# Sheet1.net
KiCad netlist of a schematic drawn in Altium Designer
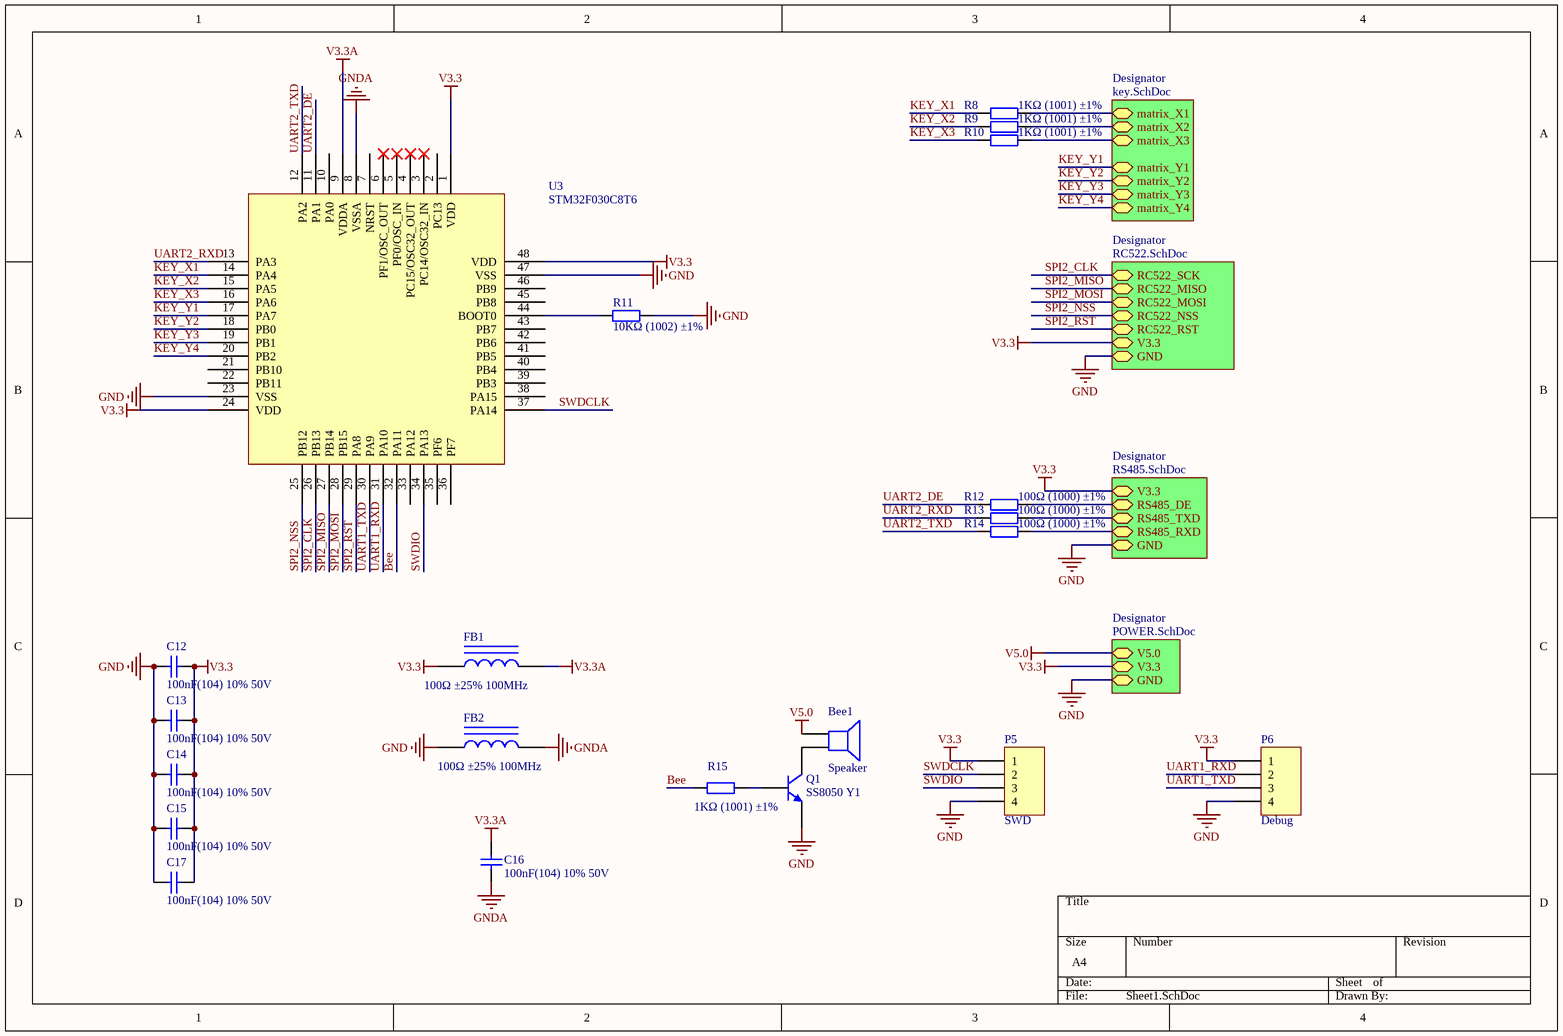
[diagram p0: Sheet1.SchDoc]

(export (version "E")
  (design (tool "Eeschema 10.0.6"))
  (components
    (comp (ref "Bee1")
      (value "Speaker")
      (footprint "Bee")
      (description "Loudspeaker")
      (fields (field (name "PUBLISHER") "Altium Limited"))
      (libsource (lib "Miscellaneous Devices") (part "Speaker"))
    )
    (comp (ref "C12")
      (value "100nF(104) 10% 50V")
      (footprint "0805_C")
      (description "贴片电容")
      (libsource (lib "Miscellaneous Devices LC") (part "0805 100nF(104) 10% 50V"))
    )
    (comp (ref "C13")
      (value "100nF(104) 10% 50V")
      (footprint "0805_C")
      (description "贴片电容")
      (libsource (lib "Miscellaneous Devices LC") (part "0805 100nF(104) 10% 50V"))
    )
    (comp (ref "C14")
      (value "100nF(104) 10% 50V")
      (footprint "0805_C")
      (description "贴片电容")
      (libsource (lib "Miscellaneous Devices LC") (part "0805 100nF(104) 10% 50V"))
    )
    (comp (ref "C15")
      (value "100nF(104) 10% 50V")
      (footprint "0805_C")
      (description "贴片电容")
      (libsource (lib "Miscellaneous Devices LC") (part "0805 100nF(104) 10% 50V"))
    )
    (comp (ref "C16")
      (value "100nF(104) 10% 50V")
      (footprint "0805_C")
      (description "贴片电容")
      (libsource (lib "Miscellaneous Devices LC") (part "0805 100nF(104) 10% 50V"))
    )
    (comp (ref "C17")
      (value "100nF(104) 10% 50V")
      (footprint "0805_C")
      (description "贴片电容")
      (libsource (lib "Miscellaneous Devices LC") (part "0805 100nF(104) 10% 50V"))
    )
    (comp (ref "FB1")
      (value "100Ω ±25% 100MHz")
      (footprint "0805_L")
      (description "贴片磁珠")
      (libsource (lib "Miscellaneous Devices LC") (part "0805 100Ω 25% 100MHz"))
    )
    (comp (ref "FB2")
      (value "100Ω ±25% 100MHz")
      (footprint "0805_L")
      (description "贴片磁珠")
      (libsource (lib "Miscellaneous Devices LC") (part "0805 100Ω 25% 100MHz"))
    )
    (comp (ref "P5")
      (value "SWD")
      (footprint "HDR1X4")
      (description "Header, 4-Pin")
      (fields (field (name "PUBLISHER") "Altium Limited"))
      (libsource (lib "Miscellaneous Connectors") (part "Header 4"))
    )
    (comp (ref "P6")
      (value "Debug")
      (footprint "HDR1X4")
      (description "Header, 4-Pin")
      (fields (field (name "PUBLISHER") "Altium Limited"))
      (libsource (lib "Miscellaneous Connectors") (part "Header 4"))
    )
    (comp (ref "Q1")
      (value "SS8050 Y1")
      (footprint "SOT-23(SOT-23-3)")
      (description "三极管")
      (libsource (lib "Miscellaneous Devices LC") (part "SOT-23 SS8050 Y1"))
    )
    (comp (ref "R8")
      (value "1KΩ (1001) ±1%")
      (footprint "0805_R")
      (description "贴片电阻")
      (libsource (lib "Miscellaneous Devices LC") (part "0805 1KΩ (1001) 1%"))
    )
    (comp (ref "R9")
      (value "1KΩ (1001) ±1%")
      (footprint "0805_R")
      (description "贴片电阻")
      (libsource (lib "Miscellaneous Devices LC") (part "0805 1KΩ (1001) 1%"))
    )
    (comp (ref "R10")
      (value "1KΩ (1001) ±1%")
      (footprint "0805_R")
      (description "贴片电阻")
      (libsource (lib "Miscellaneous Devices LC") (part "0805 1KΩ (1001) 1%"))
    )
    (comp (ref "R11")
      (value "10KΩ (1002) ±1%")
      (footprint "0805_R")
      (description "贴片电阻")
      (libsource (lib "Miscellaneous Devices LC") (part "0805 10KΩ (1002) 1%"))
    )
    (comp (ref "R12")
      (value "100Ω (1000) ±1%")
      (footprint "0805_R")
      (description "贴片电阻")
      (libsource (lib "Miscellaneous Devices LC") (part "0805 100Ω (1000) 1%"))
    )
    (comp (ref "R13")
      (value "100Ω (1000) ±1%")
      (footprint "0805_R")
      (description "贴片电阻")
      (libsource (lib "Miscellaneous Devices LC") (part "0805 100Ω (1000) 1%"))
    )
    (comp (ref "R14")
      (value "100Ω (1000) ±1%")
      (footprint "0805_R")
      (description "贴片电阻")
      (libsource (lib "Miscellaneous Devices LC") (part "0805 100Ω (1000) 1%"))
    )
    (comp (ref "R15")
      (value "1KΩ (1001) ±1%")
      (footprint "0805_R")
      (description "贴片电阻")
      (libsource (lib "Miscellaneous Devices LC") (part "0805 1KΩ (1001) 1%"))
    )
    (comp (ref "U3")
      (value "STM32F030C8T6")
      (footprint "LQFP-48_7x7x05P")
      (description "ARM")
      (libsource (lib "Miscellaneous Devices LC") (part "STM32F030C8T6"))
    )
  )
  (nets
    (net (code "1") (name "/Bee") (class "Default")
      (node (ref "R15") (pin "1") (pinfunction "1_1") (pintype "passive"))
      (node (ref "U3") (pin "32") (pinfunction "PA11_32") (pintype "passive"))
    )
    (net (code "2") (name "/KEY_X1") (class "Default")
      (node (ref "R8") (pin "1") (pinfunction "1_1") (pintype "passive"))
      (node (ref "U3") (pin "14") (pinfunction "PA4_14") (pintype "passive"))
    )
    (net (code "3") (name "/KEY_X2") (class "Default")
      (node (ref "R9") (pin "1") (pinfunction "1_1") (pintype "passive"))
      (node (ref "U3") (pin "15") (pinfunction "PA5_15") (pintype "passive"))
    )
    (net (code "4") (name "/KEY_X3") (class "Default")
      (node (ref "R10") (pin "1") (pinfunction "1_1") (pintype "passive"))
      (node (ref "U3") (pin "16") (pinfunction "PA6_16") (pintype "passive"))
    )
    (net (code "5") (name "/KEY_Y1") (class "Default")
      (node (ref "U3") (pin "17") (pinfunction "PA7_17") (pintype "passive"))
    )
    (net (code "6") (name "/KEY_Y2") (class "Default")
      (node (ref "U3") (pin "18") (pinfunction "PB0_18") (pintype "passive"))
    )
    (net (code "7") (name "/KEY_Y3") (class "Default")
      (node (ref "U3") (pin "19") (pinfunction "PB1_19") (pintype "passive"))
    )
    (net (code "8") (name "/KEY_Y4") (class "Default")
      (node (ref "U3") (pin "20") (pinfunction "PB2_20") (pintype "passive"))
    )
    (net (code "9") (name "/RS485_DE") (class "Default")
      (node (ref "R12") (pin "2") (pinfunction "2_2") (pintype "passive"))
    )
    (net (code "10") (name "/RS485_RXD") (class "Default")
      (node (ref "R14") (pin "2") (pinfunction "2_2") (pintype "passive"))
    )
    (net (code "11") (name "/RS485_TXD") (class "Default")
      (node (ref "R13") (pin "2") (pinfunction "2_2") (pintype "passive"))
    )
    (net (code "12") (name "/SPI2_CLK") (class "Default")
      (node (ref "U3") (pin "26") (pinfunction "PB13_26") (pintype "passive"))
    )
    (net (code "13") (name "/SPI2_MISO") (class "Default")
      (node (ref "U3") (pin "27") (pinfunction "PB14_27") (pintype "passive"))
    )
    (net (code "14") (name "/SPI2_MOSI") (class "Default")
      (node (ref "U3") (pin "28") (pinfunction "PB15_28") (pintype "passive"))
    )
    (net (code "15") (name "/SPI2_NSS") (class "Default")
      (node (ref "U3") (pin "25") (pinfunction "PB12_25") (pintype "passive"))
    )
    (net (code "16") (name "/SPI2_RST") (class "Default")
      (node (ref "U3") (pin "29") (pinfunction "PA8_29") (pintype "passive"))
    )
    (net (code "17") (name "/SWDCLK") (class "Default")
      (node (ref "P5") (pin "2") (pinfunction "2_2") (pintype "passive"))
      (node (ref "U3") (pin "37") (pinfunction "PA14_37") (pintype "passive"))
    )
    (net (code "18") (name "/SWDIO") (class "Default")
      (node (ref "P5") (pin "3") (pinfunction "3_3") (pintype "passive"))
      (node (ref "U3") (pin "34") (pinfunction "PA13_34") (pintype "passive"))
    )
    (net (code "19") (name "/UART1_RXD") (class "Default")
      (node (ref "P6") (pin "2") (pinfunction "2_2") (pintype "passive"))
      (node (ref "U3") (pin "31") (pinfunction "PA10_31") (pintype "passive"))
    )
    (net (code "20") (name "/UART1_TXD") (class "Default")
      (node (ref "P6") (pin "3") (pinfunction "3_3") (pintype "passive"))
      (node (ref "U3") (pin "30") (pinfunction "PA9_30") (pintype "passive"))
    )
    (net (code "21") (name "/UART2_DE") (class "Default")
      (node (ref "R12") (pin "1") (pinfunction "1_1") (pintype "passive"))
      (node (ref "U3") (pin "11") (pinfunction "PA1_11") (pintype "passive"))
    )
    (net (code "22") (name "/UART2_RXD") (class "Default")
      (node (ref "R13") (pin "1") (pinfunction "1_1") (pintype "passive"))
      (node (ref "U3") (pin "13") (pinfunction "PA3_13") (pintype "passive"))
    )
    (net (code "23") (name "/UART2_TXD") (class "Default")
      (node (ref "R14") (pin "1") (pinfunction "1_1") (pintype "passive"))
      (node (ref "U3") (pin "12") (pinfunction "PA2_12") (pintype "passive"))
    )
    (net (code "24") (name "/matrix_X1") (class "Default")
      (node (ref "R8") (pin "2") (pinfunction "2_2") (pintype "passive"))
    )
    (net (code "25") (name "/matrix_X2") (class "Default")
      (node (ref "R9") (pin "2") (pinfunction "2_2") (pintype "passive"))
    )
    (net (code "26") (name "/matrix_X3") (class "Default")
      (node (ref "R10") (pin "2") (pinfunction "2_2") (pintype "passive"))
    )
    (net (code "27") (name "GND") (class "Default")
      (node (ref "C12") (pin "1") (pinfunction "1_1") (pintype "passive"))
      (node (ref "C13") (pin "1") (pinfunction "1_1") (pintype "passive"))
      (node (ref "C14") (pin "1") (pinfunction "1_1") (pintype "passive"))
      (node (ref "C15") (pin "1") (pinfunction "1_1") (pintype "passive"))
      (node (ref "C17") (pin "1") (pinfunction "1_1") (pintype "passive"))
      (node (ref "FB2") (pin "1") (pinfunction "1_1") (pintype "passive"))
      (node (ref "P5") (pin "4") (pinfunction "4_4") (pintype "passive"))
      (node (ref "P6") (pin "4") (pinfunction "4_4") (pintype "passive"))
      (node (ref "Q1") (pin "2") (pinfunction "E_2") (pintype "passive"))
      (node (ref "R11") (pin "2") (pinfunction "2_2") (pintype "passive"))
      (node (ref "U3") (pin "23") (pinfunction "VSS_23") (pintype "passive"))
      (node (ref "U3") (pin "47") (pinfunction "VSS_47") (pintype "passive"))
    )
    (net (code "28") (name "GNDA") (class "Default")
      (node (ref "C16") (pin "1") (pinfunction "1_1") (pintype "passive"))
      (node (ref "FB2") (pin "2") (pinfunction "2_2") (pintype "passive"))
      (node (ref "U3") (pin "8") (pinfunction "VSSA_8") (pintype "passive"))
    )
    (net (code "29") (name "Net-(Q1-B)") (class "Default")
      (node (ref "Q1") (pin "1") (pinfunction "B_1") (pintype "passive"))
      (node (ref "R15") (pin "2") (pinfunction "2_2") (pintype "passive"))
    )
    (net (code "30") (name "Net-(Q1-C)") (class "Default")
      (node (ref "Bee1") (pin "2") (pinfunction "2_2") (pintype "passive"))
      (node (ref "Q1") (pin "3") (pinfunction "C_3") (pintype "passive"))
    )
    (net (code "31") (name "Net-(U3-BOOT0)") (class "Default")
      (node (ref "R11") (pin "1") (pinfunction "1_1") (pintype "passive"))
      (node (ref "U3") (pin "44") (pinfunction "BOOT0_44") (pintype "passive"))
    )
    (net (code "32") (name "V3.3") (class "Default")
      (node (ref "C12") (pin "2") (pinfunction "2_2") (pintype "passive"))
      (node (ref "C13") (pin "2") (pinfunction "2_2") (pintype "passive"))
      (node (ref "C14") (pin "2") (pinfunction "2_2") (pintype "passive"))
      (node (ref "C15") (pin "2") (pinfunction "2_2") (pintype "passive"))
      (node (ref "C17") (pin "2") (pinfunction "2_2") (pintype "passive"))
      (node (ref "FB1") (pin "1") (pinfunction "1_1") (pintype "passive"))
      (node (ref "P5") (pin "1") (pinfunction "1_1") (pintype "passive"))
      (node (ref "P6") (pin "1") (pinfunction "1_1") (pintype "passive"))
      (node (ref "U3") (pin "1") (pinfunction "VDD_1") (pintype "passive"))
      (node (ref "U3") (pin "24") (pinfunction "VDD_24") (pintype "passive"))
      (node (ref "U3") (pin "48") (pinfunction "VDD_48") (pintype "passive"))
    )
    (net (code "33") (name "V3.3A") (class "Default")
      (node (ref "C16") (pin "2") (pinfunction "2_2") (pintype "passive"))
      (node (ref "FB1") (pin "2") (pinfunction "2_2") (pintype "passive"))
      (node (ref "U3") (pin "9") (pinfunction "VDDA_9") (pintype "passive"))
    )
    (net (code "34") (name "V5.0") (class "Default")
      (node (ref "Bee1") (pin "1") (pinfunction "1_1") (pintype "passive"))
    )
    (net (code "35") (name "unconnected-(U3-NRST-Pad7)") (class "Default")
      (node (ref "U3") (pin "7") (pinfunction "NRST_7") (pintype "passive"))
    )
    (net (code "36") (name "unconnected-(U3-PA0-Pad10)") (class "Default")
      (node (ref "U3") (pin "10") (pinfunction "PA0_10") (pintype "passive"))
    )
    (net (code "37") (name "unconnected-(U3-PA12-Pad33)") (class "Default")
      (node (ref "U3") (pin "33") (pinfunction "PA12_33") (pintype "passive"))
    )
    (net (code "38") (name "unconnected-(U3-PA15-Pad38)") (class "Default")
      (node (ref "U3") (pin "38") (pinfunction "PA15_38") (pintype "passive"))
    )
    (net (code "39") (name "unconnected-(U3-PB3-Pad39)") (class "Default")
      (node (ref "U3") (pin "39") (pinfunction "PB3_39") (pintype "passive"))
    )
    (net (code "40") (name "unconnected-(U3-PB4-Pad40)") (class "Default")
      (node (ref "U3") (pin "40") (pinfunction "PB4_40") (pintype "passive"))
    )
    (net (code "41") (name "unconnected-(U3-PB5-Pad41)") (class "Default")
      (node (ref "U3") (pin "41") (pinfunction "PB5_41") (pintype "passive"))
    )
    (net (code "42") (name "unconnected-(U3-PB6-Pad42)") (class "Default")
      (node (ref "U3") (pin "42") (pinfunction "PB6_42") (pintype "passive"))
    )
    (net (code "43") (name "unconnected-(U3-PB7-Pad43)") (class "Default")
      (node (ref "U3") (pin "43") (pinfunction "PB7_43") (pintype "passive"))
    )
    (net (code "44") (name "unconnected-(U3-PB8-Pad45)") (class "Default")
      (node (ref "U3") (pin "45") (pinfunction "PB8_45") (pintype "passive"))
    )
    (net (code "45") (name "unconnected-(U3-PB9-Pad46)") (class "Default")
      (node (ref "U3") (pin "46") (pinfunction "PB9_46") (pintype "passive"))
    )
    (net (code "46") (name "unconnected-(U3-PB10-Pad21)") (class "Default")
      (node (ref "U3") (pin "21") (pinfunction "PB10_21") (pintype "passive"))
    )
    (net (code "47") (name "unconnected-(U3-PB11-Pad22)") (class "Default")
      (node (ref "U3") (pin "22") (pinfunction "PB11_22") (pintype "passive"))
    )
    (net (code "48") (name "unconnected-(U3-PC13-Pad2)") (class "Default")
      (node (ref "U3") (pin "2") (pinfunction "PC13_2") (pintype "passive"))
    )
    (net (code "49") (name "unconnected-(U3-PC14{slash}OSC32_IN-Pad3)") (class "Default")
      (node (ref "U3") (pin "3") (pinfunction "PC14/OSC32_IN_3") (pintype "passive+no_connect"))
    )
    (net (code "50") (name "unconnected-(U3-PC15{slash}OSC32_OUT-Pad4)") (class "Default")
      (node (ref "U3") (pin "4") (pinfunction "PC15/OSC32_OUT_4") (pintype "passive+no_connect"))
    )
    (net (code "51") (name "unconnected-(U3-PF0{slash}OSC_IN-Pad5)") (class "Default")
      (node (ref "U3") (pin "5") (pinfunction "PF0/OSC_IN_5") (pintype "passive+no_connect"))
    )
    (net (code "52") (name "unconnected-(U3-PF1{slash}OSC_OUT-Pad6)") (class "Default")
      (node (ref "U3") (pin "6") (pinfunction "PF1/OSC_OUT_6") (pintype "passive+no_connect"))
    )
    (net (code "53") (name "unconnected-(U3-PF6-Pad35)") (class "Default")
      (node (ref "U3") (pin "35") (pinfunction "PF6_35") (pintype "passive"))
    )
    (net (code "54") (name "unconnected-(U3-PF7-Pad36)") (class "Default")
      (node (ref "U3") (pin "36") (pinfunction "PF7_36") (pintype "passive"))
    )
  )
)
